# adapter.net
KiCad netlist of a schematic drawn in EAGLE
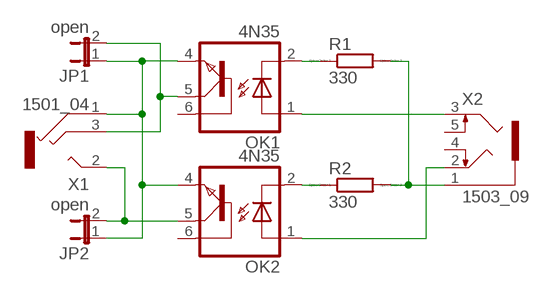
[diagram p0: schematic, sheet 1]

(export (version "E")
  (design (tool "Eeschema 10.0.6"))
  (components
    (comp (ref "JP1")
      (value "open")
      (footprint "eagle-import:JP1")
      (libsource (lib "eagle-import") (part "JP1E"))
    )
    (comp (ref "JP2")
      (value "open")
      (footprint "eagle-import:JP1")
      (libsource (lib "eagle-import") (part "JP1E"))
    )
    (comp (ref "OK1")
      (value "4N35")
      (footprint "eagle-import:DIL06")
      (fields (field (name "MF") "FAIRCHILD SEMICONDUCTOR") (field (name "MF_1") "VISHAY"))
      (libsource (lib "eagle-import") (part "4N35"))
    )
    (comp (ref "OK2")
      (value "4N35")
      (footprint "eagle-import:DIL06")
      (fields (field (name "MF") "FAIRCHILD SEMICONDUCTOR") (field (name "MF_1") "VISHAY"))
      (libsource (lib "eagle-import") (part "4N35"))
    )
    (comp (ref "R1")
      (value "330")
      (footprint "eagle-import:0207_10")
      (libsource (lib "eagle-import") (part "R0207/10"))
    )
    (comp (ref "R2")
      (value "330")
      (footprint "eagle-import:0207_10")
      (libsource (lib "eagle-import") (part "R0207/10"))
    )
    (comp (ref "X1")
      (value "1501_04")
      (footprint "eagle-import:1501_05")
      (libsource (lib "eagle-import") (part "1501_04"))
    )
    (comp (ref "X2")
      (value "1503_09")
      (footprint "eagle-import:1503_09")
      (libsource (lib "eagle-import") (part "1503_09"))
    )
  )
  (nets
    (net (code "1") (name "Net-(OK1-A)") (class "Default")
      (node (ref "OK1") (pin "1") (pinfunction "A_1") (pintype "passive"))
      (node (ref "X2") (pin "3") (pinfunction "3_3") (pintype "passive"))
    )
    (net (code "2") (name "Net-(OK1-C)") (class "Default")
      (node (ref "OK1") (pin "2") (pinfunction "C_2") (pintype "passive"))
      (node (ref "R1") (pin "1") (pinfunction "1_1") (pintype "passive"))
    )
    (net (code "3") (name "Net-(OK1-COL)") (class "Default")
      (node (ref "JP1") (pin "2") (pinfunction "2_2") (pintype "passive"))
      (node (ref "OK1") (pin "5") (pinfunction "COL_5") (pintype "passive"))
      (node (ref "X1") (pin "3") (pinfunction "3_3") (pintype "passive"))
    )
    (net (code "4") (name "Net-(OK1-EMI)") (class "Default")
      (node (ref "JP1") (pin "1") (pinfunction "1_1") (pintype "passive"))
      (node (ref "JP2") (pin "1") (pinfunction "1_1") (pintype "passive"))
      (node (ref "OK1") (pin "4") (pinfunction "EMI_4") (pintype "passive"))
      (node (ref "OK2") (pin "4") (pinfunction "EMI_4") (pintype "passive"))
      (node (ref "X1") (pin "1") (pinfunction "1_1") (pintype "passive"))
    )
    (net (code "5") (name "Net-(OK2-A)") (class "Default")
      (node (ref "OK2") (pin "1") (pinfunction "A_1") (pintype "passive"))
      (node (ref "X2") (pin "2") (pinfunction "2_2") (pintype "passive"))
    )
    (net (code "6") (name "Net-(OK2-C)") (class "Default")
      (node (ref "OK2") (pin "2") (pinfunction "C_2") (pintype "passive"))
      (node (ref "R2") (pin "1") (pinfunction "1_1") (pintype "passive"))
    )
    (net (code "7") (name "Net-(OK2-COL)") (class "Default")
      (node (ref "JP2") (pin "2") (pinfunction "2_2") (pintype "passive"))
      (node (ref "OK2") (pin "5") (pinfunction "COL_5") (pintype "passive"))
      (node (ref "X1") (pin "2") (pinfunction "2_2") (pintype "passive"))
    )
    (net (code "8") (name "Net-(R1-Pad2)") (class "Default")
      (node (ref "R1") (pin "2") (pinfunction "2_2") (pintype "passive"))
      (node (ref "R2") (pin "2") (pinfunction "2_2") (pintype "passive"))
      (node (ref "X2") (pin "1") (pinfunction "1_1") (pintype "passive"))
    )
    (net (code "9") (name "unconnected-(OK1-BAS-Pad6)") (class "Default")
      (node (ref "OK1") (pin "6") (pinfunction "BAS_6") (pintype "passive"))
    )
    (net (code "10") (name "unconnected-(OK2-BAS-Pad6)") (class "Default")
      (node (ref "OK2") (pin "6") (pinfunction "BAS_6") (pintype "passive"))
    )
    (net (code "11") (name "unconnected-(X2-Pad4)") (class "Default")
      (node (ref "X2") (pin "4") (pinfunction "4_4") (pintype "passive"))
    )
    (net (code "12") (name "unconnected-(X2-Pad5)") (class "Default")
      (node (ref "X2") (pin "5") (pinfunction "5_5") (pintype "passive"))
    )
  )
)
